# PD_Controller.net
KiCad netlist of a schematic drawn in Altium Designer
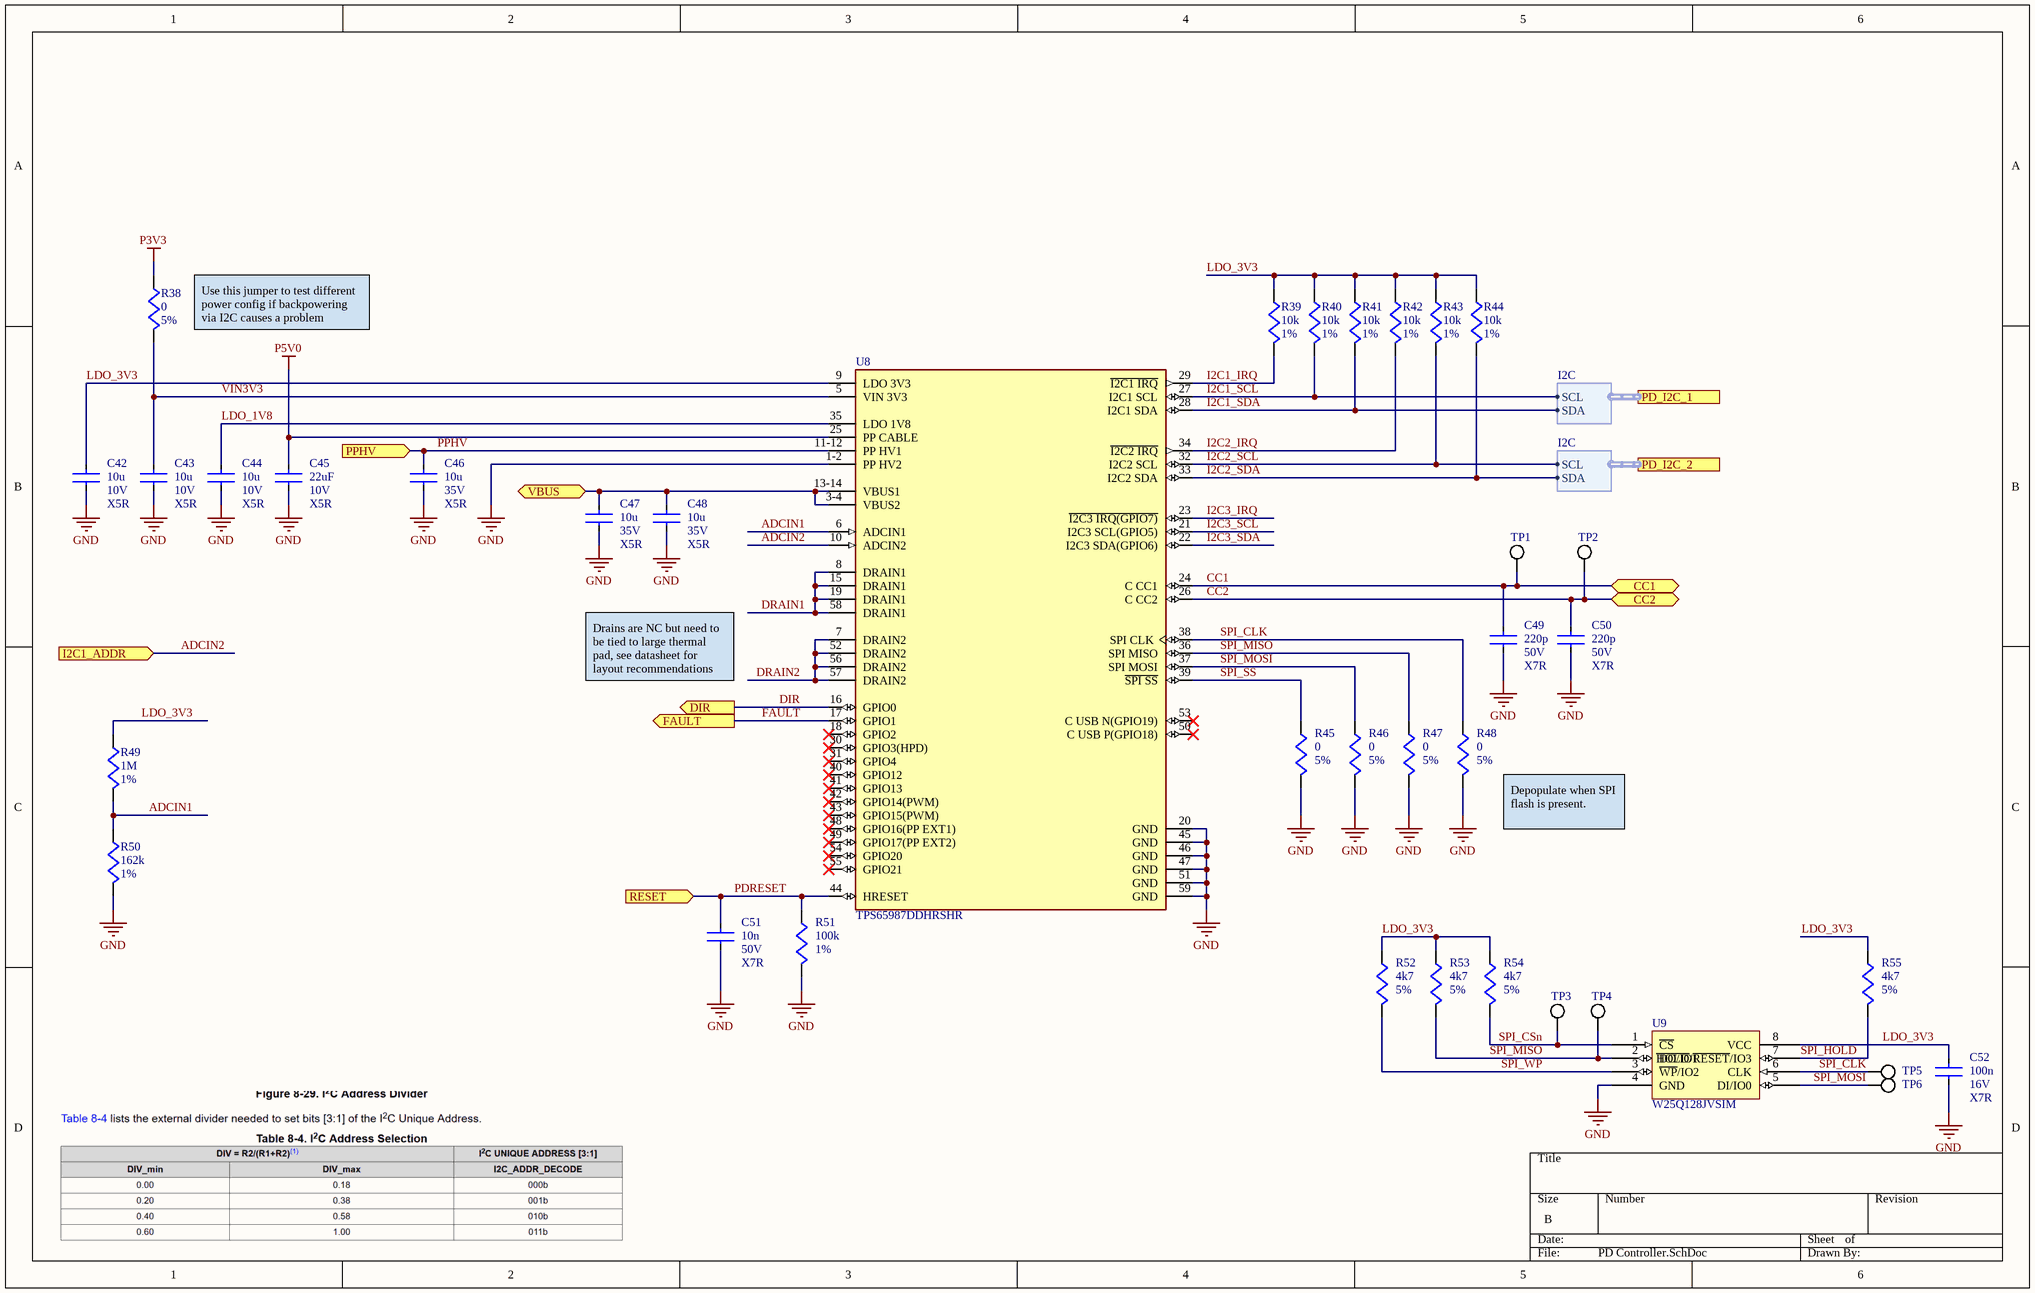
[diagram p0: PD Controller.SchDoc]

(export (version "E")
  (design (tool "Eeschema 10.0.6"))
  (components
    (comp (ref "C42")
      (value "10u")
      (footprint "CAPC1005X06N")
      (description "10uF 10V 0402 20% X5R CAP MLCC")
      (fields
        (field (name "VOLTAGE") "10V")
        (field (name "DIELECTRIC") "X5R")
        (field (name "LCSC PART #") "C527590")
        (field (name "Comment") "10uF 10V 0402")
      )
      (libsource (lib "CWRU Motorsports") (part "Capacitor"))
    )
    (comp (ref "C43")
      (value "10u")
      (footprint "CAPC1005X06N")
      (description "10uF 10V 0402 20% X5R CAP MLCC")
      (fields
        (field (name "VOLTAGE") "10V")
        (field (name "DIELECTRIC") "X5R")
        (field (name "LCSC PART #") "C527590")
        (field (name "Comment") "10uF 10V 0402")
      )
      (libsource (lib "CWRU Motorsports") (part "Capacitor"))
    )
    (comp (ref "C44")
      (value "10u")
      (footprint "CAPC1005X06N")
      (description "10uF 10V 0402 20% X5R CAP MLCC")
      (fields
        (field (name "VOLTAGE") "10V")
        (field (name "DIELECTRIC") "X5R")
        (field (name "LCSC PART #") "C527590")
        (field (name "Comment") "10uF 10V 0402")
      )
      (libsource (lib "CWRU Motorsports") (part "Capacitor"))
    )
    (comp (ref "C45")
      (value "22uF")
      (footprint "CAPC1608X08N")
      (description "10V 22uF X5R ±20% 0603 Multilayer Ceramic Capacitors MLCC - SMD/SMT ROHS")
      (fields
        (field (name "VOLTAGE") "10V")
        (field (name "DIELECTRIC") "X5R")
        (field (name "LCSC PART #") "C86295")
        (field (name "Comment") "22uF 10V 0603 X5R")
      )
      (libsource (lib "CWRU Motorsports") (part "Capacitor"))
    )
    (comp (ref "C46")
      (value "10u")
      (footprint "CAPC1608X08N")
      (description "35V 10uF X5R ±20% 0603 Multilayer Ceramic Capacitors MLCC - SMD/SMT ROHS")
      (fields
        (field (name "VOLTAGE") "35V")
        (field (name "DIELECTRIC") "X5R")
        (field (name "LCSC PART #") "C194427")
        (field (name "Comment") "10uF 35V 0603")
      )
      (libsource (lib "CWRU Motorsports") (part "Capacitor"))
    )
    (comp (ref "C47")
      (value "10u")
      (footprint "CAPC1608X08N")
      (description "35V 10uF X5R ±20% 0603 Multilayer Ceramic Capacitors MLCC - SMD/SMT ROHS")
      (fields
        (field (name "VOLTAGE") "35V")
        (field (name "DIELECTRIC") "X5R")
        (field (name "LCSC PART #") "C194427")
        (field (name "Comment") "10uF 35V 0603")
      )
      (libsource (lib "CWRU Motorsports") (part "Capacitor"))
    )
    (comp (ref "C48")
      (value "10u")
      (footprint "CAPC1608X08N")
      (description "35V 10uF X5R ±20% 0603 Multilayer Ceramic Capacitors MLCC - SMD/SMT ROHS")
      (fields
        (field (name "VOLTAGE") "35V")
        (field (name "DIELECTRIC") "X5R")
        (field (name "LCSC PART #") "C194427")
        (field (name "Comment") "10uF 35V 0603")
      )
      (libsource (lib "CWRU Motorsports") (part "Capacitor"))
    )
    (comp (ref "C49")
      (value "220p")
      (footprint "CAPC1005X06N")
      (description "50V 220pF X7R ±10% 0402 Multilayer Ceramic Capacitors MLCC - SMD/SMT ROHS")
      (fields
        (field (name "VOLTAGE") "50V")
        (field (name "DIELECTRIC") "X7R")
        (field (name "LCSC PART #") "C107025")
        (field (name "Comment") "220pF 50V 0402")
      )
      (libsource (lib "CWRU Motorsports") (part "Capacitor"))
    )
    (comp (ref "C50")
      (value "220p")
      (footprint "CAPC1005X06N")
      (description "50V 220pF X7R ±10% 0402 Multilayer Ceramic Capacitors MLCC - SMD/SMT ROHS")
      (fields
        (field (name "VOLTAGE") "50V")
        (field (name "DIELECTRIC") "X7R")
        (field (name "LCSC PART #") "C107025")
        (field (name "Comment") "220pF 50V 0402")
      )
      (libsource (lib "CWRU Motorsports") (part "Capacitor"))
    )
    (comp (ref "C51")
      (value "10n")
      (footprint "CAPC1005X06N")
      (description "50V 10nF X7R ±10% 0402 Multilayer Ceramic Capacitors MLCC - SMD/SMT ROHS")
      (fields
        (field (name "VOLTAGE") "50V")
        (field (name "DIELECTRIC") "X7R")
        (field (name "LCSC PART #") "C60133")
        (field (name "Comment") "10n 50V X7R 0402")
      )
      (libsource (lib "CWRU Motorsports") (part "Capacitor"))
    )
    (comp (ref "C52")
      (value "100n")
      (footprint "CAPC1005X06N")
      (description "16V 100nF X7R ±10% 0402 Multilayer Ceramic Capacitors MLCC - SMD/SMT ROHS")
      (fields
        (field (name "VOLTAGE") "16V")
        (field (name "DIELECTRIC") "X7R")
        (field (name "LCSC PART #") "C1525")
        (field (name "Comment") "100nF 16V 0402")
      )
      (libsource (lib "CWRU Motorsports") (part "Capacitor"))
    )
    (comp (ref "R38")
      (value "0")
      (footprint "RESC1005X04M")
      (description "62.5mW Thick Film Resistors 50V ±5% 0Ω 0402 Chip Resistor - Surface Mount ROHS")
      (fields
        (field (name "TOLERANCE") "5%")
        (field (name "LCSC PART #") "C60485")
        (field (name "Comment") "0 Ohm 1% 0402")
      )
      (libsource (lib "CWRU Motorsports") (part "Resistor"))
    )
    (comp (ref "R39")
      (value "10k")
      (footprint "RESC1005X04M")
      (description "62.5mW Thick Film Resistors 50V ±100ppm/℃ ±1% 10kΩ 0402 Chip Resistor - Surface Mount ROHS")
      (fields
        (field (name "TOLERANCE") "1%")
        (field (name "LCSC PART #") "C60490")
        (field (name "Comment") "10k 1% 0402")
      )
      (libsource (lib "CWRU Motorsports") (part "Resistor"))
    )
    (comp (ref "R40")
      (value "10k")
      (footprint "RESC1005X04M")
      (description "62.5mW Thick Film Resistors 50V ±100ppm/℃ ±1% 10kΩ 0402 Chip Resistor - Surface Mount ROHS")
      (fields
        (field (name "TOLERANCE") "1%")
        (field (name "LCSC PART #") "C60490")
        (field (name "Comment") "10k 1% 0402")
      )
      (libsource (lib "CWRU Motorsports") (part "Resistor"))
    )
    (comp (ref "R41")
      (value "10k")
      (footprint "RESC1005X04M")
      (description "62.5mW Thick Film Resistors 50V ±100ppm/℃ ±1% 10kΩ 0402 Chip Resistor - Surface Mount ROHS")
      (fields
        (field (name "TOLERANCE") "1%")
        (field (name "LCSC PART #") "C60490")
        (field (name "Comment") "10k 1% 0402")
      )
      (libsource (lib "CWRU Motorsports") (part "Resistor"))
    )
    (comp (ref "R42")
      (value "10k")
      (footprint "RESC1005X04M")
      (description "62.5mW Thick Film Resistors 50V ±100ppm/℃ ±1% 10kΩ 0402 Chip Resistor - Surface Mount ROHS")
      (fields
        (field (name "TOLERANCE") "1%")
        (field (name "LCSC PART #") "C60490")
        (field (name "Comment") "10k 1% 0402")
      )
      (libsource (lib "CWRU Motorsports") (part "Resistor"))
    )
    (comp (ref "R43")
      (value "10k")
      (footprint "RESC1005X04M")
      (description "62.5mW Thick Film Resistors 50V ±100ppm/℃ ±1% 10kΩ 0402 Chip Resistor - Surface Mount ROHS")
      (fields
        (field (name "TOLERANCE") "1%")
        (field (name "LCSC PART #") "C60490")
        (field (name "Comment") "10k 1% 0402")
      )
      (libsource (lib "CWRU Motorsports") (part "Resistor"))
    )
    (comp (ref "R44")
      (value "10k")
      (footprint "RESC1005X04M")
      (description "62.5mW Thick Film Resistors 50V ±100ppm/℃ ±1% 10kΩ 0402 Chip Resistor - Surface Mount ROHS")
      (fields
        (field (name "TOLERANCE") "1%")
        (field (name "LCSC PART #") "C60490")
        (field (name "Comment") "10k 1% 0402")
      )
      (libsource (lib "CWRU Motorsports") (part "Resistor"))
    )
    (comp (ref "R45")
      (value "0")
      (footprint "RESC1005X04M")
      (description "62.5mW Thick Film Resistors 50V ±5% 0Ω 0402 Chip Resistor - Surface Mount ROHS")
      (fields
        (field (name "TOLERANCE") "5%")
        (field (name "LCSC PART #") "C60485")
        (field (name "Comment") "0 Ohm 1% 0402")
      )
      (libsource (lib "CWRU Motorsports") (part "Resistor"))
    )
    (comp (ref "R46")
      (value "0")
      (footprint "RESC1005X04M")
      (description "62.5mW Thick Film Resistors 50V ±5% 0Ω 0402 Chip Resistor - Surface Mount ROHS")
      (fields
        (field (name "TOLERANCE") "5%")
        (field (name "LCSC PART #") "C60485")
        (field (name "Comment") "0 Ohm 1% 0402")
      )
      (libsource (lib "CWRU Motorsports") (part "Resistor"))
    )
    (comp (ref "R47")
      (value "0")
      (footprint "RESC1005X04M")
      (description "62.5mW Thick Film Resistors 50V ±5% 0Ω 0402 Chip Resistor - Surface Mount ROHS")
      (fields
        (field (name "TOLERANCE") "5%")
        (field (name "LCSC PART #") "C60485")
        (field (name "Comment") "0 Ohm 1% 0402")
      )
      (libsource (lib "CWRU Motorsports") (part "Resistor"))
    )
    (comp (ref "R48")
      (value "0")
      (footprint "RESC1005X04M")
      (description "62.5mW Thick Film Resistors 50V ±5% 0Ω 0402 Chip Resistor - Surface Mount ROHS")
      (fields
        (field (name "TOLERANCE") "5%")
        (field (name "LCSC PART #") "C60485")
        (field (name "Comment") "0 Ohm 1% 0402")
      )
      (libsource (lib "CWRU Motorsports") (part "Resistor"))
    )
    (comp (ref "R49")
      (value "1M")
      (footprint "RESC1005X04M")
      (description "62.5mW Thick Film Resistors 50V ±100ppm/℃ ±1% 1MΩ 0402 Chip Resistor - Surface Mount ROHS")
      (fields
        (field (name "TOLERANCE") "1%")
        (field (name "LCSC PART #") "C138033")
        (field (name "Comment") "1M 1% 0402")
      )
      (libsource (lib "CWRU Motorsports") (part "Resistor"))
    )
    (comp (ref "R50")
      (value "162k")
      (footprint "RESC1005X04M")
      (description "62.5mW Thick Film Resistors 50V ±100ppm/℃ ±1% 162kΩ 0402 Chip Resistor - Surface Mount ROHS")
      (fields
        (field (name "TOLERANCE") "1%")
        (field (name "LCSC PART #") "C54068")
        (field (name "Comment") "162k 1% 0402")
      )
      (libsource (lib "CWRU Motorsports") (part "Resistor"))
    )
    (comp (ref "R51")
      (value "100k")
      (footprint "RESC1005X04M")
      (description "62.5mW Thick Film Resistors 50V ±100ppm/℃ ±1% 100kΩ 0402 Chip Resistor - Surface Mount ROHS")
      (fields
        (field (name "TOLERANCE") "1%")
        (field (name "LCSC PART #") "C60491")
        (field (name "Comment") "100k 1% 0402")
      )
      (libsource (lib "CWRU Motorsports") (part "Resistor"))
    )
    (comp (ref "R52")
      (value "4k7")
      (footprint "RESC1005X04M")
      (description "62.5mW Thick Film Resistors 50V ±100ppm/℃ ±5% 4.7kΩ 0402 Chip Resistor - Surface Mount ROHS")
      (fields
        (field (name "TOLERANCE") "5%")
        (field (name "LCSC PART #") "C105870")
        (field (name "Comment") "4.7k 5% 0402")
      )
      (libsource (lib "CWRU Motorsports") (part "Resistor"))
    )
    (comp (ref "R53")
      (value "4k7")
      (footprint "RESC1005X04M")
      (description "62.5mW Thick Film Resistors 50V ±100ppm/℃ ±5% 4.7kΩ 0402 Chip Resistor - Surface Mount ROHS")
      (fields
        (field (name "TOLERANCE") "5%")
        (field (name "LCSC PART #") "C105870")
        (field (name "Comment") "4.7k 5% 0402")
      )
      (libsource (lib "CWRU Motorsports") (part "Resistor"))
    )
    (comp (ref "R54")
      (value "4k7")
      (footprint "RESC1005X04M")
      (description "62.5mW Thick Film Resistors 50V ±100ppm/℃ ±5% 4.7kΩ 0402 Chip Resistor - Surface Mount ROHS")
      (fields
        (field (name "TOLERANCE") "5%")
        (field (name "LCSC PART #") "C105870")
        (field (name "Comment") "4.7k 5% 0402")
      )
      (libsource (lib "CWRU Motorsports") (part "Resistor"))
    )
    (comp (ref "R55")
      (value "4k7")
      (footprint "RESC1005X04M")
      (description "62.5mW Thick Film Resistors 50V ±100ppm/℃ ±5% 4.7kΩ 0402 Chip Resistor - Surface Mount ROHS")
      (fields
        (field (name "TOLERANCE") "5%")
        (field (name "LCSC PART #") "C105870")
        (field (name "Comment") "4.7k 5% 0402")
      )
      (libsource (lib "CWRU Motorsports") (part "Resistor"))
    )
    (comp (ref "TP1")
      (value "45mil Test Point")
      (footprint "45mil Test Point Footprint")
      (description "45mil SMD test point")
      (libsource (lib "CWRU Motorsports") (part "Test Point"))
    )
    (comp (ref "TP2")
      (value "45mil Test Point")
      (footprint "45mil Test Point Footprint")
      (description "45mil SMD test point")
      (libsource (lib "CWRU Motorsports") (part "Test Point"))
    )
    (comp (ref "TP3")
      (value "45mil Test Point")
      (footprint "45mil Test Point Footprint")
      (description "45mil SMD test point")
      (libsource (lib "CWRU Motorsports") (part "Test Point"))
    )
    (comp (ref "TP4")
      (value "45mil Test Point")
      (footprint "45mil Test Point Footprint")
      (description "45mil SMD test point")
      (libsource (lib "CWRU Motorsports") (part "Test Point"))
    )
    (comp (ref "TP5")
      (value "45mil Test Point")
      (footprint "45mil Test Point Footprint")
      (description "45mil SMD test point")
      (libsource (lib "CWRU Motorsports") (part "Test Point"))
    )
    (comp (ref "TP6")
      (value "45mil Test Point")
      (footprint "45mil Test Point Footprint")
      (description "45mil SMD test point")
      (libsource (lib "CWRU Motorsports") (part "Test Point"))
    )
    (comp (ref "U8")
      (value "TPS65987DDHRSHR")
      (footprint "FP-RSH0056E-MFG")
      (description "USB Type-C™ and USB PD controller with integrated power switches 56-VQFN -10 to 75")
      (libsource (lib "CWRU Motorsports") (part "ac31af8065ecbcdb16e42a170e0950f"))
    )
    (comp (ref "U9")
      (value "W25Q128JVSIM")
      (footprint "SOIC127P790X216-8N")
      (description "NOR Flash Serial (SPI, Dual SPI, Quad SPI) 3V/3.3V 128M-bit 16M x 8 6ns 8-Pin SOIC Tube")
      (libsource (lib "CWRU Motorsports") (part "W25Q128JVSIM-Symbol-1"))
    )
  )
  (nets
    (net (code "2") (name "/ADCIN1") (class "Default")
      (node (ref "R49") (pin "2") (pinfunction "2_2") (pintype "passive"))
      (node (ref "R50") (pin "1") (pinfunction "1_1") (pintype "passive"))
      (node (ref "U8") (pin "6") (pinfunction "ADCIN1_6") (pintype "input"))
    )
    (net (code "3") (name "/ADCIN2") (class "Default")
      (node (ref "U8") (pin "10") (pinfunction "ADCIN2_10") (pintype "input"))
    )
    (net (code "4") (name "/CC1") (class "Default")
      (node (ref "C49") (pin "1") (pinfunction "1_1") (pintype "passive"))
      (node (ref "TP1") (pin "0") (pinfunction "0_0") (pintype "passive"))
      (node (ref "U8") (pin "24") (pinfunction "C_CC1_24") (pintype "bidirectional"))
    )
    (net (code "5") (name "/CC2") (class "Default")
      (node (ref "C50") (pin "1") (pinfunction "1_1") (pintype "passive"))
      (node (ref "TP2") (pin "0") (pinfunction "0_0") (pintype "passive"))
      (node (ref "U8") (pin "26") (pinfunction "C_CC2_26") (pintype "bidirectional"))
    )
    (net (code "6") (name "/DIR") (class "Default")
      (node (ref "U8") (pin "16") (pinfunction "GPIO0_16") (pintype "bidirectional"))
    )
    (net (code "7") (name "/DRAIN1") (class "Default")
      (node (ref "U8") (pin "15") (pinfunction "DRAIN1_15") (pintype "passive"))
      (node (ref "U8") (pin "19") (pinfunction "DRAIN1_19") (pintype "passive"))
      (node (ref "U8") (pin "58") (pinfunction "DRAIN1_58") (pintype "passive"))
      (node (ref "U8") (pin "8") (pinfunction "DRAIN1_8") (pintype "passive"))
    )
    (net (code "8") (name "/DRAIN2") (class "Default")
      (node (ref "U8") (pin "52") (pinfunction "DRAIN2_52") (pintype "passive"))
      (node (ref "U8") (pin "56") (pinfunction "DRAIN2_56") (pintype "passive"))
      (node (ref "U8") (pin "57") (pinfunction "DRAIN2_57") (pintype "passive"))
      (node (ref "U8") (pin "7") (pinfunction "DRAIN2_7") (pintype "passive"))
    )
    (net (code "9") (name "/FAULT") (class "Default")
      (node (ref "U8") (pin "17") (pinfunction "GPIO1_17") (pintype "bidirectional"))
    )
    (net (code "10") (name "/I2C1_IRQ") (class "Default")
      (node (ref "R39") (pin "2") (pinfunction "2_2") (pintype "passive"))
      (node (ref "U8") (pin "29") (pinfunction "~{I2C1_IRQ}_29") (pintype "output"))
    )
    (net (code "11") (name "/I2C1_SCL") (class "Default")
      (node (ref "R40") (pin "2") (pinfunction "2_2") (pintype "passive"))
      (node (ref "U8") (pin "27") (pinfunction "I2C1_SCL_27") (pintype "bidirectional"))
    )
    (net (code "12") (name "/I2C1_SDA") (class "Default")
      (node (ref "R41") (pin "2") (pinfunction "2_2") (pintype "passive"))
      (node (ref "U8") (pin "28") (pinfunction "I2C1_SDA_28") (pintype "bidirectional"))
    )
    (net (code "13") (name "/I2C2_IRQ") (class "Default")
      (node (ref "R42") (pin "2") (pinfunction "2_2") (pintype "passive"))
      (node (ref "U8") (pin "34") (pinfunction "~{I2C2_IRQ}_34") (pintype "output"))
    )
    (net (code "14") (name "/I2C2_SCL") (class "Default")
      (node (ref "R43") (pin "2") (pinfunction "2_2") (pintype "passive"))
      (node (ref "U8") (pin "32") (pinfunction "I2C2_SCL_32") (pintype "bidirectional"))
    )
    (net (code "15") (name "/I2C2_SDA") (class "Default")
      (node (ref "R44") (pin "2") (pinfunction "2_2") (pintype "passive"))
      (node (ref "U8") (pin "33") (pinfunction "I2C2_SDA_33") (pintype "bidirectional"))
    )
    (net (code "16") (name "/I2C3_IRQ") (class "Default")
      (node (ref "U8") (pin "23") (pinfunction "~{I2C3_IRQ(GPIO7)}_23") (pintype "bidirectional"))
    )
    (net (code "17") (name "/I2C3_SCL") (class "Default")
      (node (ref "U8") (pin "21") (pinfunction "I2C3_SCL(GPIO5)_21") (pintype "bidirectional"))
    )
    (net (code "18") (name "/I2C3_SDA") (class "Default")
      (node (ref "U8") (pin "22") (pinfunction "I2C3_SDA(GPIO6)_22") (pintype "bidirectional"))
    )
    (net (code "19") (name "/LDO_1V8") (class "Default")
      (node (ref "C44") (pin "1") (pinfunction "1_1") (pintype "passive"))
      (node (ref "U8") (pin "35") (pinfunction "LDO_1V8_35") (pintype "power_in"))
    )
    (net (code "20") (name "/LDO_3V3") (class "Default")
      (node (ref "C42") (pin "1") (pinfunction "1_1") (pintype "passive"))
      (node (ref "C52") (pin "1") (pinfunction "1_1") (pintype "passive"))
      (node (ref "R39") (pin "1") (pinfunction "1_1") (pintype "passive"))
      (node (ref "R40") (pin "1") (pinfunction "1_1") (pintype "passive"))
      (node (ref "R41") (pin "1") (pinfunction "1_1") (pintype "passive"))
      (node (ref "R42") (pin "1") (pinfunction "1_1") (pintype "passive"))
      (node (ref "R43") (pin "1") (pinfunction "1_1") (pintype "passive"))
      (node (ref "R44") (pin "1") (pinfunction "1_1") (pintype "passive"))
      (node (ref "R49") (pin "1") (pinfunction "1_1") (pintype "passive"))
      (node (ref "R52") (pin "1") (pinfunction "1_1") (pintype "passive"))
      (node (ref "R53") (pin "1") (pinfunction "1_1") (pintype "passive"))
      (node (ref "R54") (pin "1") (pinfunction "1_1") (pintype "passive"))
      (node (ref "R55") (pin "1") (pinfunction "1_1") (pintype "passive"))
      (node (ref "U8") (pin "9") (pinfunction "LDO_3V3_9") (pintype "power_in"))
      (node (ref "U9") (pin "8") (pinfunction "VCC_8") (pintype "power_in"))
    )
    (net (code "21") (name "/PDRESET") (class "Default")
      (node (ref "C51") (pin "1") (pinfunction "1_1") (pintype "passive"))
      (node (ref "R51") (pin "1") (pinfunction "1_1") (pintype "passive"))
      (node (ref "U8") (pin "44") (pinfunction "HRESET_44") (pintype "bidirectional"))
    )
    (net (code "22") (name "/PPHV") (class "Default")
      (node (ref "C46") (pin "1") (pinfunction "1_1") (pintype "passive"))
      (node (ref "U8") (pin "11-12") (pinfunction "PP_HV1_11-12") (pintype "power_in"))
    )
    (net (code "23") (name "/SPI_CLK") (class "Default")
      (node (ref "R48") (pin "1") (pinfunction "1_1") (pintype "passive"))
      (node (ref "TP5") (pin "0") (pinfunction "0_0") (pintype "passive"))
      (node (ref "U8") (pin "38") (pinfunction "SPI_CLK_38") (pintype "bidirectional"))
      (node (ref "U9") (pin "6") (pinfunction "CLK_6") (pintype "input"))
    )
    (net (code "24") (name "/SPI_CSn") (class "Default")
      (node (ref "R54") (pin "2") (pinfunction "2_2") (pintype "passive"))
      (node (ref "TP3") (pin "0") (pinfunction "0_0") (pintype "passive"))
      (node (ref "U9") (pin "1") (pinfunction "~{CS}_1") (pintype "input"))
    )
    (net (code "25") (name "/SPI_HOLD") (class "Default")
      (node (ref "R55") (pin "2") (pinfunction "2_2") (pintype "passive"))
      (node (ref "U9") (pin "7") (pinfunction "~{HOLD}/~{RESET}/IO3_7") (pintype "bidirectional"))
    )
    (net (code "26") (name "/SPI_MISO") (class "Default")
      (node (ref "R47") (pin "1") (pinfunction "1_1") (pintype "passive"))
      (node (ref "R53") (pin "2") (pinfunction "2_2") (pintype "passive"))
      (node (ref "TP4") (pin "0") (pinfunction "0_0") (pintype "passive"))
      (node (ref "U8") (pin "36") (pinfunction "SPI_MISO_36") (pintype "bidirectional"))
      (node (ref "U9") (pin "2") (pinfunction "DO/IO1_2") (pintype "bidirectional"))
    )
    (net (code "27") (name "/SPI_MOSI") (class "Default")
      (node (ref "R46") (pin "1") (pinfunction "1_1") (pintype "passive"))
      (node (ref "TP6") (pin "0") (pinfunction "0_0") (pintype "passive"))
      (node (ref "U8") (pin "37") (pinfunction "SPI_MOSI_37") (pintype "bidirectional"))
      (node (ref "U9") (pin "5") (pinfunction "DI/IO0_5") (pintype "bidirectional"))
    )
    (net (code "28") (name "/SPI_SS") (class "Default")
      (node (ref "R45") (pin "1") (pinfunction "1_1") (pintype "passive"))
      (node (ref "U8") (pin "39") (pinfunction "~{SPI_SS}_39") (pintype "bidirectional"))
    )
    (net (code "29") (name "/SPI_WP") (class "Default")
      (node (ref "R52") (pin "2") (pinfunction "2_2") (pintype "passive"))
      (node (ref "U9") (pin "3") (pinfunction "~{WP}/IO2_3") (pintype "bidirectional"))
    )
    (net (code "30") (name "/VBUS") (class "Default")
      (node (ref "C47") (pin "1") (pinfunction "1_1") (pintype "passive"))
      (node (ref "C48") (pin "1") (pinfunction "1_1") (pintype "passive"))
      (node (ref "U8") (pin "13-14") (pinfunction "VBUS1_13-14") (pintype "power_in"))
      (node (ref "U8") (pin "3-4") (pinfunction "VBUS2_3-4") (pintype "power_in"))
    )
    (net (code "31") (name "/VIN3V3") (class "Default")
      (node (ref "C43") (pin "1") (pinfunction "1_1") (pintype "passive"))
      (node (ref "R38") (pin "2") (pinfunction "2_2") (pintype "passive"))
      (node (ref "U8") (pin "5") (pinfunction "VIN_3V3_5") (pintype "power_in"))
    )
    (net (code "33") (name "GND") (class "Default")
      (node (ref "C42") (pin "2") (pinfunction "2_2") (pintype "passive"))
      (node (ref "C43") (pin "2") (pinfunction "2_2") (pintype "passive"))
      (node (ref "C44") (pin "2") (pinfunction "2_2") (pintype "passive"))
      (node (ref "C45") (pin "2") (pinfunction "2_2") (pintype "passive"))
      (node (ref "C46") (pin "2") (pinfunction "2_2") (pintype "passive"))
      (node (ref "C47") (pin "2") (pinfunction "2_2") (pintype "passive"))
      (node (ref "C48") (pin "2") (pinfunction "2_2") (pintype "passive"))
      (node (ref "C49") (pin "2") (pinfunction "2_2") (pintype "passive"))
      (node (ref "C50") (pin "2") (pinfunction "2_2") (pintype "passive"))
      (node (ref "C51") (pin "2") (pinfunction "2_2") (pintype "passive"))
      (node (ref "C52") (pin "2") (pinfunction "2_2") (pintype "passive"))
      (node (ref "R45") (pin "2") (pinfunction "2_2") (pintype "passive"))
      (node (ref "R46") (pin "2") (pinfunction "2_2") (pintype "passive"))
      (node (ref "R47") (pin "2") (pinfunction "2_2") (pintype "passive"))
      (node (ref "R48") (pin "2") (pinfunction "2_2") (pintype "passive"))
      (node (ref "R50") (pin "2") (pinfunction "2_2") (pintype "passive"))
      (node (ref "R51") (pin "2") (pinfunction "2_2") (pintype "passive"))
      (node (ref "U8") (pin "1-2") (pinfunction "PP_HV2_1-2") (pintype "power_in"))
      (node (ref "U8") (pin "20") (pinfunction "GND_20") (pintype "power_in"))
      (node (ref "U8") (pin "45") (pinfunction "GND_45") (pintype "power_in"))
      (node (ref "U8") (pin "46") (pinfunction "GND_46") (pintype "power_in"))
      (node (ref "U8") (pin "47") (pinfunction "GND_47") (pintype "power_in"))
      (node (ref "U8") (pin "51") (pinfunction "GND_51") (pintype "power_in"))
      (node (ref "U8") (pin "59") (pinfunction "GND_59") (pintype "power_in"))
      (node (ref "U9") (pin "4") (pinfunction "GND_4") (pintype "power_in"))
    )
    (net (code "34") (name "P3V3") (class "Default")
      (node (ref "R38") (pin "1") (pinfunction "1_1") (pintype "passive"))
    )
    (net (code "35") (name "P5V0") (class "Default")
      (node (ref "C45") (pin "1") (pinfunction "1_1") (pintype "passive"))
      (node (ref "U8") (pin "25") (pinfunction "PP_CABLE_25") (pintype "power_in"))
    )
    (net (code "36") (name "unconnected-(U8-C_USB_N(GPIO19)-Pad53)") (class "Default")
      (node (ref "U8") (pin "53") (pinfunction "C_USB_N(GPIO19)_53") (pintype "bidirectional+no_connect"))
    )
    (net (code "37") (name "unconnected-(U8-C_USB_P(GPIO18)-Pad50)") (class "Default")
      (node (ref "U8") (pin "50") (pinfunction "C_USB_P(GPIO18)_50") (pintype "bidirectional+no_connect"))
    )
    (net (code "38") (name "unconnected-(U8-GPIO2-Pad18)") (class "Default")
      (node (ref "U8") (pin "18") (pinfunction "GPIO2_18") (pintype "bidirectional+no_connect"))
    )
    (net (code "39") (name "unconnected-(U8-GPIO3(HPD)-Pad30)") (class "Default")
      (node (ref "U8") (pin "30") (pinfunction "GPIO3(HPD)_30") (pintype "bidirectional+no_connect"))
    )
    (net (code "40") (name "unconnected-(U8-GPIO4-Pad31)") (class "Default")
      (node (ref "U8") (pin "31") (pinfunction "GPIO4_31") (pintype "bidirectional+no_connect"))
    )
    (net (code "41") (name "unconnected-(U8-GPIO12-Pad40)") (class "Default")
      (node (ref "U8") (pin "40") (pinfunction "GPIO12_40") (pintype "bidirectional+no_connect"))
    )
    (net (code "42") (name "unconnected-(U8-GPIO13-Pad41)") (class "Default")
      (node (ref "U8") (pin "41") (pinfunction "GPIO13_41") (pintype "bidirectional+no_connect"))
    )
    (net (code "43") (name "unconnected-(U8-GPIO14(PWM)-Pad42)") (class "Default")
      (node (ref "U8") (pin "42") (pinfunction "GPIO14(PWM)_42") (pintype "bidirectional+no_connect"))
    )
    (net (code "44") (name "unconnected-(U8-GPIO15(PWM)-Pad43)") (class "Default")
      (node (ref "U8") (pin "43") (pinfunction "GPIO15(PWM)_43") (pintype "bidirectional+no_connect"))
    )
    (net (code "45") (name "unconnected-(U8-GPIO16(PP_EXT1)-Pad48)") (class "Default")
      (node (ref "U8") (pin "48") (pinfunction "GPIO16(PP_EXT1)_48") (pintype "bidirectional+no_connect"))
    )
    (net (code "46") (name "unconnected-(U8-GPIO17(PP_EXT2)-Pad49)") (class "Default")
      (node (ref "U8") (pin "49") (pinfunction "GPIO17(PP_EXT2)_49") (pintype "bidirectional+no_connect"))
    )
    (net (code "47") (name "unconnected-(U8-GPIO20-Pad54)") (class "Default")
      (node (ref "U8") (pin "54") (pinfunction "GPIO20_54") (pintype "bidirectional+no_connect"))
    )
    (net (code "48") (name "unconnected-(U8-GPIO21-Pad55)") (class "Default")
      (node (ref "U8") (pin "55") (pinfunction "GPIO21_55") (pintype "bidirectional+no_connect"))
    )
  )
)
